# gps_and_sensor_board.net
KiCad netlist of a schematic drawn in EAGLE
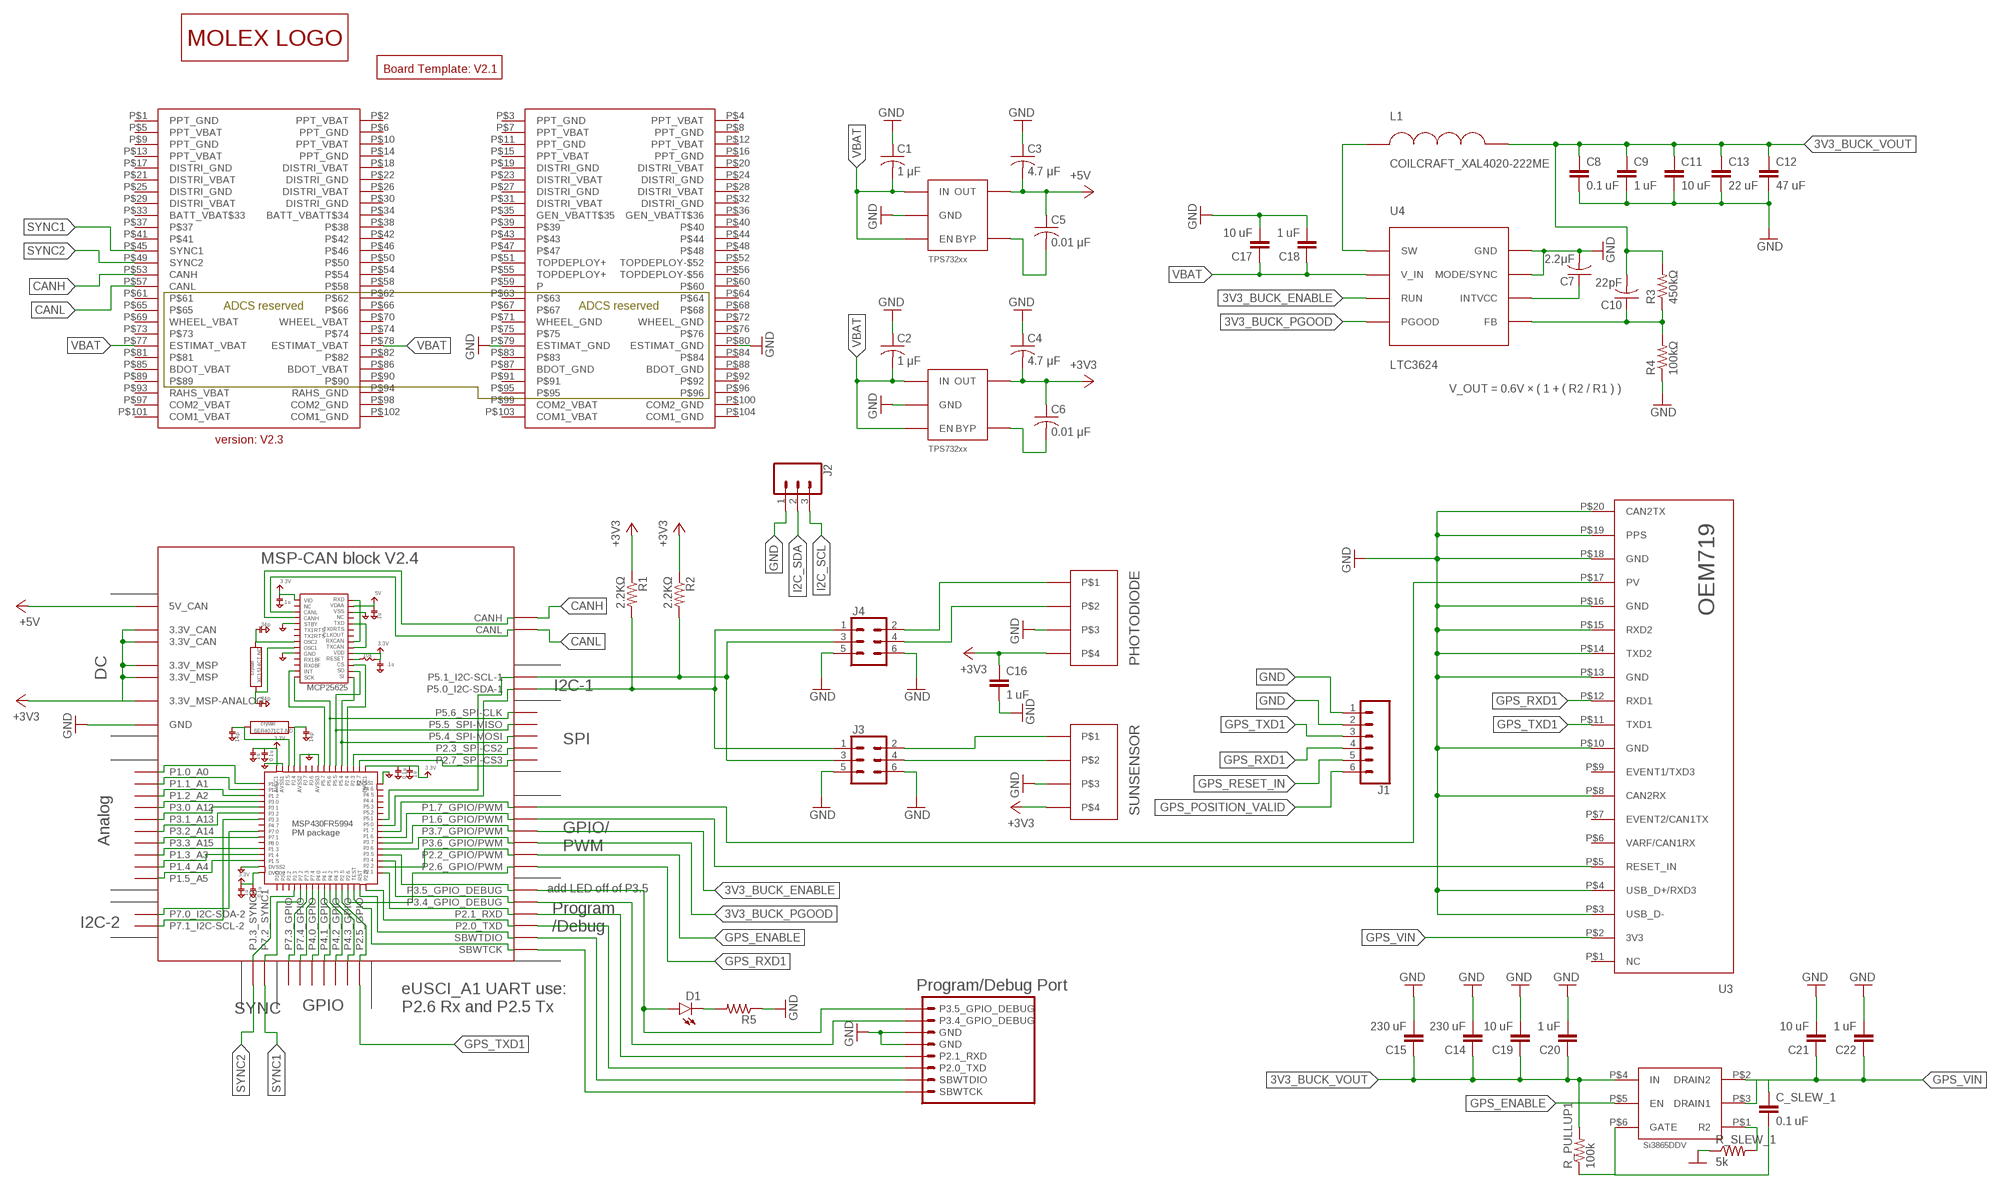
[diagram p0: schematic, sheet 1]

(export (version "E")
  (design (tool "Eeschema 10.0.6"))
  (components
    (comp (ref "B1")
      (value "BOARD_TEMPLATE1")
      (footprint "eagle-import:BOARD_TEMPLATE")
      (libsource (lib "eagle-import") (part "BOARD_TEMPLATE1"))
    )
    (comp (ref "BLK1")
      (value "MSP-CAN_BLOCK")
      (footprint "eagle-import:MSP-CAN_BLOCK")
      (libsource (lib "eagle-import") (part "MSP-CAN_BLOCK"))
    )
    (comp (ref "C1")
      (value "1 μF")
      (footprint "eagle-import:C0805")
      (libsource (lib "eagle-import") (part "C-USC0805"))
    )
    (comp (ref "C2")
      (value "1 μF")
      (footprint "eagle-import:C0805")
      (libsource (lib "eagle-import") (part "C-USC0805"))
    )
    (comp (ref "C3")
      (value "4.7 μF")
      (footprint "eagle-import:C0805")
      (libsource (lib "eagle-import") (part "C-USC0805"))
    )
    (comp (ref "C4")
      (value "4.7 μF")
      (footprint "eagle-import:C0805")
      (libsource (lib "eagle-import") (part "C-USC0805"))
    )
    (comp (ref "C5")
      (value "0.01 μF")
      (footprint "eagle-import:C0805")
      (libsource (lib "eagle-import") (part "C-USC0805"))
    )
    (comp (ref "C6")
      (value "0.01 μF")
      (footprint "eagle-import:C0805")
      (libsource (lib "eagle-import") (part "C-USC0805"))
    )
    (comp (ref "C7")
      (value "2.2μF")
      (footprint "eagle-import:C0805")
      (libsource (lib "eagle-import") (part "C-USC0805"))
    )
    (comp (ref "C8")
      (value "0.1 uF")
      (footprint "eagle-import:0805")
      (libsource (lib "eagle-import") (part "CAPACITOR0805"))
    )
    (comp (ref "C9")
      (value "1 uF")
      (footprint "eagle-import:0805")
      (libsource (lib "eagle-import") (part "CAPACITOR0805"))
    )
    (comp (ref "C10")
      (value "22pF")
      (footprint "eagle-import:C0805")
      (libsource (lib "eagle-import") (part "C-USC0805"))
    )
    (comp (ref "C11")
      (value "10 uF")
      (footprint "eagle-import:0805")
      (libsource (lib "eagle-import") (part "CAPACITOR0805"))
    )
    (comp (ref "C12")
      (value "47 uF")
      (footprint "eagle-import:1206")
      (libsource (lib "eagle-import") (part "CAPACITOR1206"))
    )
    (comp (ref "C13")
      (value "22 uF")
      (footprint "eagle-import:1206")
      (libsource (lib "eagle-import") (part "CAPACITOR1206"))
    )
    (comp (ref "C14")
      (value "230 uF")
      (footprint "eagle-import:PANASONIC_SVPG")
      (libsource (lib "eagle-import") (part "CAPACITORPANASONIC_16SVPG270M"))
    )
    (comp (ref "C15")
      (value "230 uF")
      (footprint "eagle-import:PANASONIC_SVPG")
      (libsource (lib "eagle-import") (part "CAPACITORPANASONIC_16SVPG270M"))
    )
    (comp (ref "C16")
      (value "1 uF")
      (footprint "eagle-import:0805")
      (libsource (lib "eagle-import") (part "CAPACITOR0805"))
    )
    (comp (ref "C17")
      (value "10 uF")
      (footprint "eagle-import:0805")
      (libsource (lib "eagle-import") (part "CAPACITOR0805"))
    )
    (comp (ref "C18")
      (value "1 uF")
      (footprint "eagle-import:0805")
      (libsource (lib "eagle-import") (part "CAPACITOR0805"))
    )
    (comp (ref "C19")
      (value "10 uF")
      (footprint "eagle-import:0805")
      (libsource (lib "eagle-import") (part "CAPACITOR0805"))
    )
    (comp (ref "C20")
      (value "1 uF")
      (footprint "eagle-import:0805")
      (libsource (lib "eagle-import") (part "CAPACITOR0805"))
    )
    (comp (ref "C21")
      (value "10 uF")
      (footprint "eagle-import:0805")
      (libsource (lib "eagle-import") (part "CAPACITOR0805"))
    )
    (comp (ref "C22")
      (value "1 uF")
      (footprint "eagle-import:0805")
      (libsource (lib "eagle-import") (part "CAPACITOR0805"))
    )
    (comp (ref "CONN1")
      (value "PC104_CONNECTOR")
      (footprint "eagle-import:PC104_CONNECTOR")
      (libsource (lib "eagle-import") (part "PC104_CONNECTOR"))
    )
    (comp (ref "C_SLEW_1")
      (value "0.1 uF")
      (footprint "eagle-import:0805")
      (libsource (lib "eagle-import") (part "CAPACITOR0805"))
    )
    (comp (ref "D1")
      (value "LED")
      (footprint "eagle-import:LED-1206")
      (libsource (lib "eagle-import") (part "LED"))
    )
    (comp (ref "J1")
      (value "CONN_06LOCK")
      (footprint "eagle-import:1X06_LOCK")
      (libsource (lib "eagle-import") (part "CONN_06LOCK"))
    )
    (comp (ref "J2")
      (value "CONN_03LOCK")
      (footprint "eagle-import:1X03_LOCK")
      (libsource (lib "eagle-import") (part "CONN_03LOCK"))
    )
    (comp (ref "J3")
      (value "CONN_03X22X3_SILK_MALE_PTH")
      (footprint "eagle-import:2X3")
      (libsource (lib "eagle-import") (part "CONN_03X22X3_SILK_MALE_PTH"))
    )
    (comp (ref "J4")
      (value "CONN_03X22X3_SILK_MALE_PTH")
      (footprint "eagle-import:2X3")
      (libsource (lib "eagle-import") (part "CONN_03X22X3_SILK_MALE_PTH"))
    )
    (comp (ref "L1")
      (value "COILCRAFT_XAL4020-222ME")
      (footprint "eagle-import:COILCRAFT_XAL4020")
      (libsource (lib "eagle-import") (part "COILCRAFT_XAL4020-222ME"))
    )
    (comp (ref "PHOTODIODE")
      (value "PICOLOCK_4")
      (footprint "eagle-import:PICOLOCK_4")
      (libsource (lib "eagle-import") (part "PICOLOCK_4"))
    )
    (comp (ref "R1")
      (value "2.2KΩ")
      (footprint "eagle-import:R0805")
      (libsource (lib "eagle-import") (part "R-US_R0805"))
    )
    (comp (ref "R2")
      (value "2.2KΩ")
      (footprint "eagle-import:R0805")
      (libsource (lib "eagle-import") (part "R-US_R0805"))
    )
    (comp (ref "R3")
      (value "450kΩ")
      (footprint "eagle-import:R0805")
      (libsource (lib "eagle-import") (part "R-US_R0805"))
    )
    (comp (ref "R4")
      (value "100kΩ")
      (footprint "eagle-import:R0805")
      (libsource (lib "eagle-import") (part "R-US_R0805"))
    )
    (comp (ref "R5")
      (value "RESISTOR0805")
      (footprint "eagle-import:0805")
      (libsource (lib "eagle-import") (part "RESISTOR0805"))
    )
    (comp (ref "R_PULLUP1")
      (value "100k")
      (footprint "eagle-import:0805")
      (libsource (lib "eagle-import") (part "RESISTOR0805"))
    )
    (comp (ref "R_SLEW_1")
      (value "5k")
      (footprint "eagle-import:0805")
      (libsource (lib "eagle-import") (part "RESISTOR0805"))
    )
    (comp (ref "SUNSENSOR")
      (value "PICOLOCK_4")
      (footprint "eagle-import:PICOLOCK_4")
      (libsource (lib "eagle-import") (part "PICOLOCK_4"))
    )
    (comp (ref "U$1")
      (value "LOGO_MOLEX")
      (footprint "eagle-import:LOGO_MOLEX")
      (libsource (lib "eagle-import") (part "LOGO_MOLEX"))
    )
    (comp (ref "U$2")
      (value "PROGRAM/DEBUG_PORT")
      (footprint "eagle-import:1X08_CONNECTOR")
      (libsource (lib "eagle-import") (part "PROGRAM/DEBUG_PORT"))
    )
    (comp (ref "U$3")
      (value "SI3865DDV")
      (footprint "eagle-import:TSOP-6")
      (libsource (lib "eagle-import") (part "SI3865DDV"))
    )
    (comp (ref "U1")
      (value "TPS732XX")
      (footprint "eagle-import:SOT-23-5")
      (libsource (lib "eagle-import") (part "TPS732XX"))
    )
    (comp (ref "U2")
      (value "TPS732XX")
      (footprint "eagle-import:SOT-23-5")
      (libsource (lib "eagle-import") (part "TPS732XX"))
    )
    (comp (ref "U3")
      (value "OEM719")
      (footprint "eagle-import:OEM719")
      (libsource (lib "eagle-import") (part "OEM719"))
    )
    (comp (ref "U4")
      (value "LTC3624")
      (footprint "eagle-import:LTC3624")
      (libsource (lib "eagle-import") (part "LTC3624"))
    )
  )
  (nets
    (net (code "1") (name "+3V3") (class "Default")
      (node (ref "BLK1") (pin "3.3V@CAN1") (pinfunction "3.3V_CAN_3.3V@CAN1") (pintype "bidirectional"))
      (node (ref "BLK1") (pin "3.3V@CAN2") (pinfunction "3.3V_CAN_3.3V@CAN2") (pintype "bidirectional"))
      (node (ref "BLK1") (pin "3.3V@MSP1") (pinfunction "3.3V_MSP_3.3V@MSP1") (pintype "bidirectional"))
      (node (ref "BLK1") (pin "3.3V@MSP2") (pinfunction "3.3V_MSP_3.3V@MSP2") (pintype "bidirectional"))
      (node (ref "BLK1") (pin "3.3V_ANALOG@MSP2") (pinfunction "3.3V_MSP-ANALOG_3.3V_ANALOG@MSP2") (pintype "bidirectional"))
      (node (ref "C16") (pin "1") (pinfunction "1_1") (pintype "passive"))
      (node (ref "C4") (pin "2") (pinfunction "2_2") (pintype "passive"))
      (node (ref "C6") (pin "1") (pinfunction "1_1") (pintype "passive"))
      (node (ref "PHOTODIODE") (pin "P$4") (pinfunction "P$4_P$4") (pintype "bidirectional"))
      (node (ref "R1") (pin "1") (pinfunction "1_1") (pintype "passive"))
      (node (ref "R2") (pin "1") (pinfunction "1_1") (pintype "passive"))
      (node (ref "SUNSENSOR") (pin "P$4") (pinfunction "P$4_P$4") (pintype "bidirectional"))
      (node (ref "U2") (pin "P$5") (pinfunction "OUT_P$5") (pintype "bidirectional"))
    )
    (net (code "2") (name "+5V") (class "Default")
      (node (ref "BLK1") (pin "5V") (pinfunction "5V_CAN_5V") (pintype "bidirectional"))
      (node (ref "C3") (pin "2") (pinfunction "2_2") (pintype "passive"))
      (node (ref "C5") (pin "1") (pinfunction "1_1") (pintype "passive"))
      (node (ref "U1") (pin "P$5") (pinfunction "OUT_P$5") (pintype "bidirectional"))
    )
    (net (code "3") (name "3V3_BUCK_ENABLE") (class "Default")
      (node (ref "BLK1") (pin "P3.7_GPIO/PWM") (pinfunction "P3.7_GPIO/PWM_P3.7_GPIO/PWM") (pintype "bidirectional"))
      (node (ref "U4") (pin "RUN") (pinfunction "RUN_RUN") (pintype "bidirectional"))
    )
    (net (code "4") (name "3V3_BUCK_PGOOD") (class "Default")
      (node (ref "BLK1") (pin "P3.6_GPIO/PWM") (pinfunction "P3.6_GPIO/PWM_P3.6_GPIO/PWM") (pintype "bidirectional"))
      (node (ref "U4") (pin "PGOOD") (pinfunction "PGOOD_PGOOD") (pintype "bidirectional"))
    )
    (net (code "5") (name "3V3_BUCK_VOUT") (class "Default")
      (node (ref "C10") (pin "2") (pinfunction "2_2") (pintype "passive"))
      (node (ref "C11") (pin "1") (pinfunction "1_1") (pintype "passive"))
      (node (ref "C12") (pin "1") (pinfunction "1_1") (pintype "passive"))
      (node (ref "C13") (pin "1") (pinfunction "1_1") (pintype "passive"))
      (node (ref "C14") (pin "POS") (pinfunction "1_POS") (pintype "passive"))
      (node (ref "C15") (pin "POS") (pinfunction "1_POS") (pintype "passive"))
      (node (ref "C19") (pin "1") (pinfunction "1_1") (pintype "passive"))
      (node (ref "C20") (pin "1") (pinfunction "1_1") (pintype "passive"))
      (node (ref "C8") (pin "1") (pinfunction "1_1") (pintype "passive"))
      (node (ref "C9") (pin "1") (pinfunction "1_1") (pintype "passive"))
      (node (ref "L1") (pin "P$2") (pinfunction "P$2_P$2") (pintype "bidirectional"))
      (node (ref "R3") (pin "2") (pinfunction "2_2") (pintype "passive"))
      (node (ref "R_PULLUP1") (pin "2") (pinfunction "2_2") (pintype "passive"))
      (node (ref "U$3") (pin "P$4") (pinfunction "IN_P$4") (pintype "bidirectional"))
    )
    (net (code "6") (name "CANH") (class "Default")
      (node (ref "BLK1") (pin "CANH") (pinfunction "CANH_CANH") (pintype "bidirectional"))
      (node (ref "CONN1") (pin "P$53") (pinfunction "CANH_P$53") (pintype "bidirectional"))
    )
    (net (code "7") (name "CANL") (class "Default")
      (node (ref "BLK1") (pin "CANL") (pinfunction "CANL_CANL") (pintype "bidirectional"))
      (node (ref "CONN1") (pin "P$57") (pinfunction "CANL_P$57") (pintype "bidirectional"))
    )
    (net (code "8") (name "GND") (class "Default")
      (node (ref "BLK1") (pin "GND@1") (pinfunction "GND_GND@1") (pintype "bidirectional"))
      (node (ref "BLK1") (pin "GND@10") (pinfunction "GND_GND@10") (pintype "bidirectional"))
      (node (ref "BLK1") (pin "GND@11") (pinfunction "GND_GND@11") (pintype "bidirectional"))
      (node (ref "BLK1") (pin "GND@12") (pinfunction "GND_GND@12") (pintype "bidirectional"))
      (node (ref "BLK1") (pin "GND@13") (pinfunction "GND_GND@13") (pintype "bidirectional"))
      (node (ref "BLK1") (pin "GND@14") (pinfunction "GND_GND@14") (pintype "bidirectional"))
      (node (ref "BLK1") (pin "GND@15") (pinfunction "GND_GND@15") (pintype "bidirectional"))
      (node (ref "BLK1") (pin "GND@16") (pinfunction "GND_GND@16") (pintype "bidirectional"))
      (node (ref "BLK1") (pin "GND@17") (pinfunction "GND_GND@17") (pintype "bidirectional"))
      (node (ref "BLK1") (pin "GND@2") (pinfunction "GND_GND@2") (pintype "bidirectional"))
      (node (ref "BLK1") (pin "GND@26") (pinfunction "GND_GND@26") (pintype "bidirectional"))
      (node (ref "BLK1") (pin "GND@3") (pinfunction "GND_GND@3") (pintype "bidirectional"))
      (node (ref "BLK1") (pin "GND@4") (pinfunction "GND_GND@4") (pintype "bidirectional"))
      (node (ref "BLK1") (pin "GND@5") (pinfunction "GND_GND@5") (pintype "bidirectional"))
      (node (ref "BLK1") (pin "GND@7") (pinfunction "GND_GND@7") (pintype "bidirectional"))
      (node (ref "BLK1") (pin "GND@8") (pinfunction "GND_GND@8") (pintype "bidirectional"))
      (node (ref "BLK1") (pin "GND@9") (pinfunction "GND_GND@9") (pintype "bidirectional"))
      (node (ref "C1") (pin "1") (pinfunction "1_1") (pintype "passive"))
      (node (ref "C11") (pin "2") (pinfunction "2_2") (pintype "passive"))
      (node (ref "C12") (pin "2") (pinfunction "2_2") (pintype "passive"))
      (node (ref "C13") (pin "2") (pinfunction "2_2") (pintype "passive"))
      (node (ref "C14") (pin "NEG") (pinfunction "2_NEG") (pintype "passive"))
      (node (ref "C15") (pin "NEG") (pinfunction "2_NEG") (pintype "passive"))
      (node (ref "C16") (pin "2") (pinfunction "2_2") (pintype "passive"))
      (node (ref "C17") (pin "2") (pinfunction "2_2") (pintype "passive"))
      (node (ref "C18") (pin "2") (pinfunction "2_2") (pintype "passive"))
      (node (ref "C19") (pin "2") (pinfunction "2_2") (pintype "passive"))
      (node (ref "C2") (pin "1") (pinfunction "1_1") (pintype "passive"))
      (node (ref "C20") (pin "2") (pinfunction "2_2") (pintype "passive"))
      (node (ref "C21") (pin "2") (pinfunction "2_2") (pintype "passive"))
      (node (ref "C22") (pin "2") (pinfunction "2_2") (pintype "passive"))
      (node (ref "C3") (pin "1") (pinfunction "1_1") (pintype "passive"))
      (node (ref "C4") (pin "1") (pinfunction "1_1") (pintype "passive"))
      (node (ref "C7") (pin "2") (pinfunction "2_2") (pintype "passive"))
      (node (ref "C8") (pin "2") (pinfunction "2_2") (pintype "passive"))
      (node (ref "C9") (pin "2") (pinfunction "2_2") (pintype "passive"))
      (node (ref "CONN1") (pin "P$79") (pinfunction "ESTIMAT_GND_P$79") (pintype "bidirectional"))
      (node (ref "CONN1") (pin "P$80") (pinfunction "ESTIMAT_GND_P$80") (pintype "bidirectional"))
      (node (ref "J1") (pin "1") (pinfunction "1_1") (pintype "passive"))
      (node (ref "J1") (pin "2") (pinfunction "2_2") (pintype "passive"))
      (node (ref "J2") (pin "1") (pinfunction "1_1") (pintype "passive"))
      (node (ref "J3") (pin "5") (pinfunction "5_5") (pintype "bidirectional"))
      (node (ref "J3") (pin "6") (pinfunction "6_6") (pintype "bidirectional"))
      (node (ref "J4") (pin "5") (pinfunction "5_5") (pintype "bidirectional"))
      (node (ref "J4") (pin "6") (pinfunction "6_6") (pintype "bidirectional"))
      (node (ref "PHOTODIODE") (pin "P$3") (pinfunction "P$3_P$3") (pintype "bidirectional"))
      (node (ref "R4") (pin "1") (pinfunction "1_1") (pintype "passive"))
      (node (ref "R5") (pin "1") (pinfunction "1_1") (pintype "passive"))
      (node (ref "R_SLEW_1") (pin "1") (pinfunction "1_1") (pintype "passive"))
      (node (ref "SUNSENSOR") (pin "P$3") (pinfunction "P$3_P$3") (pintype "bidirectional"))
      (node (ref "U$2") (pin "5") (pinfunction "GND_5") (pintype "bidirectional"))
      (node (ref "U$2") (pin "6") (pinfunction "GND_6") (pintype "bidirectional"))
      (node (ref "U1") (pin "P$2") (pinfunction "GND_P$2") (pintype "bidirectional"))
      (node (ref "U2") (pin "P$2") (pinfunction "GND_P$2") (pintype "bidirectional"))
      (node (ref "U3") (pin "P$10") (pinfunction "GND_P$10") (pintype "bidirectional"))
      (node (ref "U3") (pin "P$13") (pinfunction "GND_P$13") (pintype "bidirectional"))
      (node (ref "U3") (pin "P$14") (pinfunction "TXD2_P$14") (pintype "bidirectional"))
      (node (ref "U3") (pin "P$15") (pinfunction "RXD2_P$15") (pintype "bidirectional"))
      (node (ref "U3") (pin "P$16") (pinfunction "GND_P$16") (pintype "bidirectional"))
      (node (ref "U3") (pin "P$18") (pinfunction "GND_P$18") (pintype "bidirectional"))
      (node (ref "U3") (pin "P$19") (pinfunction "PPS_P$19") (pintype "bidirectional"))
      (node (ref "U3") (pin "P$20") (pinfunction "CAN2TX_P$20") (pintype "bidirectional"))
      (node (ref "U3") (pin "P$3") (pinfunction "USB_D-_P$3") (pintype "bidirectional"))
      (node (ref "U3") (pin "P$4") (pinfunction "USB_D+/RXD3_P$4") (pintype "bidirectional"))
      (node (ref "U3") (pin "P$8") (pinfunction "CAN2RX_P$8") (pintype "bidirectional"))
      (node (ref "U4") (pin "GND@1") (pinfunction "GND_GND@1") (pintype "bidirectional"))
      (node (ref "U4") (pin "GND@PAD") (pinfunction "GND_GND@PAD") (pintype "bidirectional"))
      (node (ref "U4") (pin "MODE/SYNC") (pinfunction "MODE/SYNC_MODE/SYNC") (pintype "bidirectional"))
    )
    (net (code "9") (name "GPS_ENABLE") (class "Default")
      (node (ref "BLK1") (pin "P2.2_GPIO/PWM") (pinfunction "P2.2_GPIO/PWM_P2.2_GPIO/PWM") (pintype "bidirectional"))
      (node (ref "U$3") (pin "P$5") (pinfunction "EN_P$5") (pintype "bidirectional"))
    )
    (net (code "10") (name "GPS_POSITION_VALID") (class "Default")
      (node (ref "BLK1") (pin "P1.7_GPIO/PWM") (pinfunction "P1.7_GPIO/PWM_P1.7_GPIO/PWM") (pintype "bidirectional"))
      (node (ref "J1") (pin "6") (pinfunction "6_6") (pintype "passive"))
      (node (ref "U3") (pin "P$17") (pinfunction "PV_P$17") (pintype "bidirectional"))
    )
    (net (code "11") (name "GPS_RESET_IN") (class "Default")
      (node (ref "BLK1") (pin "P1.6_GPIO/PWM") (pinfunction "P1.6_GPIO/PWM_P1.6_GPIO/PWM") (pintype "bidirectional"))
      (node (ref "J1") (pin "5") (pinfunction "5_5") (pintype "passive"))
      (node (ref "U3") (pin "P$5") (pinfunction "RESET_IN_P$5") (pintype "bidirectional"))
    )
    (net (code "12") (name "GPS_RXD1") (class "Default")
      (node (ref "BLK1") (pin "P2.6_GPIO/PWM") (pinfunction "P2.6_GPIO/PWM_P2.6_GPIO/PWM") (pintype "bidirectional"))
      (node (ref "J1") (pin "4") (pinfunction "4_4") (pintype "passive"))
      (node (ref "U3") (pin "P$12") (pinfunction "RXD1_P$12") (pintype "bidirectional"))
    )
    (net (code "13") (name "GPS_TXD1") (class "Default")
      (node (ref "BLK1") (pin "P2.5_GPIO") (pinfunction "P2.5_GPIO_P2.5_GPIO") (pintype "bidirectional"))
      (node (ref "J1") (pin "3") (pinfunction "3_3") (pintype "passive"))
      (node (ref "U3") (pin "P$11") (pinfunction "TXD1_P$11") (pintype "bidirectional"))
    )
    (net (code "14") (name "GPS_VIN") (class "Default")
      (node (ref "C21") (pin "1") (pinfunction "1_1") (pintype "passive"))
      (node (ref "C22") (pin "1") (pinfunction "1_1") (pintype "passive"))
      (node (ref "C_SLEW_1") (pin "1") (pinfunction "1_1") (pintype "passive"))
      (node (ref "U$3") (pin "P$2") (pinfunction "DRAIN2_P$2") (pintype "bidirectional"))
      (node (ref "U$3") (pin "P$3") (pinfunction "DRAIN1_P$3") (pintype "bidirectional"))
      (node (ref "U3") (pin "P$2") (pinfunction "3V3_P$2") (pintype "bidirectional"))
    )
    (net (code "15") (name "I2C_SCL") (class "Default")
      (node (ref "BLK1") (pin "P5.1_I2C-SCL-1") (pinfunction "P5.1_I2C-SCL-1_P5.1_I2C-SCL-1") (pintype "bidirectional"))
      (node (ref "J2") (pin "3") (pinfunction "3_3") (pintype "passive"))
      (node (ref "J3") (pin "3") (pinfunction "3_3") (pintype "bidirectional"))
      (node (ref "J4") (pin "3") (pinfunction "3_3") (pintype "bidirectional"))
      (node (ref "R2") (pin "2") (pinfunction "2_2") (pintype "passive"))
    )
    (net (code "16") (name "I2C_SDA") (class "Default")
      (node (ref "BLK1") (pin "P5.0_I2C-SDA-1") (pinfunction "P5.0_I2C-SDA-1_P5.0_I2C-SDA-1") (pintype "bidirectional"))
      (node (ref "J2") (pin "2") (pinfunction "2_2") (pintype "passive"))
      (node (ref "J3") (pin "1") (pinfunction "1_1") (pintype "bidirectional"))
      (node (ref "J4") (pin "1") (pinfunction "1_1") (pintype "bidirectional"))
      (node (ref "R1") (pin "2") (pinfunction "2_2") (pintype "passive"))
    )
    (net (code "17") (name "Net-(BLK1-PadSBWTCK)") (class "Default")
      (node (ref "BLK1") (pin "SBWTCK") (pinfunction "SBWTCK_SBWTCK") (pintype "bidirectional"))
      (node (ref "U$2") (pin "SBWTCK") (pinfunction "SBWTCK_SBWTCK") (pintype "bidirectional"))
    )
    (net (code "18") (name "Net-(C7-Pad1)") (class "Default")
      (node (ref "C7") (pin "1") (pinfunction "1_1") (pintype "passive"))
      (node (ref "U4") (pin "INTVCC") (pinfunction "INTVCC_INTVCC") (pintype "bidirectional"))
    )
    (net (code "19") (name "Net-(C10-Pad1)") (class "Default")
      (node (ref "C10") (pin "1") (pinfunction "1_1") (pintype "passive"))
      (node (ref "R3") (pin "1") (pinfunction "1_1") (pintype "passive"))
      (node (ref "R4") (pin "2") (pinfunction "2_2") (pintype "passive"))
      (node (ref "U4") (pin "FB") (pinfunction "FB_FB") (pintype "bidirectional"))
    )
    (net (code "20") (name "Net-(D1-PadC)") (class "Default")
      (node (ref "D1") (pin "C") (pinfunction "C_C") (pintype "passive"))
      (node (ref "R5") (pin "2") (pinfunction "2_2") (pintype "passive"))
    )
    (net (code "21") (name "Net-(J3-Pad2)") (class "Default")
      (node (ref "J3") (pin "2") (pinfunction "2_2") (pintype "bidirectional"))
      (node (ref "SUNSENSOR") (pin "P$1") (pinfunction "P$1_P$1") (pintype "bidirectional"))
    )
    (net (code "22") (name "Net-(J3-Pad4)") (class "Default")
      (node (ref "J3") (pin "4") (pinfunction "4_4") (pintype "bidirectional"))
      (node (ref "SUNSENSOR") (pin "P$2") (pinfunction "P$2_P$2") (pintype "bidirectional"))
    )
    (net (code "23") (name "Net-(J4-Pad2)") (class "Default")
      (node (ref "J4") (pin "2") (pinfunction "2_2") (pintype "bidirectional"))
      (node (ref "PHOTODIODE") (pin "P$1") (pinfunction "P$1_P$1") (pintype "bidirectional"))
    )
    (net (code "24") (name "Net-(J4-Pad4)") (class "Default")
      (node (ref "J4") (pin "4") (pinfunction "4_4") (pintype "bidirectional"))
      (node (ref "PHOTODIODE") (pin "P$2") (pinfunction "P$2_P$2") (pintype "bidirectional"))
    )
    (net (code "25") (name "Net-(L1-PadP$1)") (class "Default")
      (node (ref "L1") (pin "P$1") (pinfunction "P$1_P$1") (pintype "bidirectional"))
      (node (ref "U4") (pin "SW") (pinfunction "SW_SW") (pintype "bidirectional"))
    )
    (net (code "26") (name "Net-(U$2-P2.0_TXD)") (class "Default")
      (node (ref "BLK1") (pin "P2.0_TXD") (pinfunction "P2.0_TXD_P2.0_TXD") (pintype "bidirectional"))
      (node (ref "U$2") (pin "3") (pinfunction "P2.0_TXD_3") (pintype "bidirectional"))
    )
    (net (code "27") (name "Net-(U$2-P2.1_RXD)") (class "Default")
      (node (ref "BLK1") (pin "P2.1_RXD") (pinfunction "P2.1_RXD_P2.1_RXD") (pintype "bidirectional"))
      (node (ref "U$2") (pin "4") (pinfunction "P2.1_RXD_4") (pintype "bidirectional"))
    )
    (net (code "28") (name "Net-(U$2-P3.4_GPIO_DEBUG)") (class "Default")
      (node (ref "BLK1") (pin "P3.4_GPIO_DEBUG") (pinfunction "P3.4_GPIO_DEBUG_P3.4_GPIO_DEBUG") (pintype "bidirectional"))
      (node (ref "U$2") (pin "7") (pinfunction "P3.4_GPIO_DEBUG_7") (pintype "bidirectional"))
    )
    (net (code "29") (name "Net-(U$2-P3.5_GPIO_DEBUG)") (class "Default")
      (node (ref "BLK1") (pin "P3.5_GPIO_DEBUG") (pinfunction "P3.5_GPIO_DEBUG_P3.5_GPIO_DEBUG") (pintype "bidirectional"))
      (node (ref "D1") (pin "A") (pinfunction "A_A") (pintype "passive"))
      (node (ref "U$2") (pin "8") (pinfunction "P3.5_GPIO_DEBUG_8") (pintype "bidirectional"))
    )
    (net (code "30") (name "Net-(U$2-SBWTDIO)") (class "Default")
      (node (ref "BLK1") (pin "SBWTDIO") (pinfunction "SBWTDIO_SBWTDIO") (pintype "bidirectional"))
      (node (ref "U$2") (pin "2") (pinfunction "SBWTDIO_2") (pintype "bidirectional"))
    )
    (net (code "31") (name "Net-(U$3-GATE)") (class "Default")
      (node (ref "C_SLEW_1") (pin "2") (pinfunction "2_2") (pintype "passive"))
      (node (ref "R_PULLUP1") (pin "1") (pinfunction "1_1") (pintype "passive"))
      (node (ref "U$3") (pin "P$6") (pinfunction "GATE_P$6") (pintype "bidirectional"))
    )
    (net (code "32") (name "Net-(U$3-R2)") (class "Default")
      (node (ref "R_SLEW_1") (pin "2") (pinfunction "2_2") (pintype "passive"))
      (node (ref "U$3") (pin "P$1") (pinfunction "R2_P$1") (pintype "bidirectional"))
    )
    (net (code "33") (name "Net-(U1-BYP)") (class "Default")
      (node (ref "C5") (pin "2") (pinfunction "2_2") (pintype "passive"))
      (node (ref "U1") (pin "P$4") (pinfunction "BYP_P$4") (pintype "bidirectional"))
    )
    (net (code "34") (name "Net-(U2-BYP)") (class "Default")
      (node (ref "C6") (pin "2") (pinfunction "2_2") (pintype "passive"))
      (node (ref "U2") (pin "P$4") (pinfunction "BYP_P$4") (pintype "bidirectional"))
    )
    (net (code "35") (name "SYNC1") (class "Default")
      (node (ref "BLK1") (pin "P7.2_SYNC1") (pinfunction "P7.2_SYNC1_P7.2_SYNC1") (pintype "bidirectional"))
      (node (ref "CONN1") (pin "P$45") (pinfunction "SYNC1_P$45") (pintype "bidirectional"))
    )
    (net (code "36") (name "SYNC2") (class "Default")
      (node (ref "BLK1") (pin "PJ.3_SYNC2") (pinfunction "PJ.3_SYNC2_PJ.3_SYNC2") (pintype "bidirectional"))
      (node (ref "CONN1") (pin "P$49") (pinfunction "SYNC2_P$49") (pintype "bidirectional"))
    )
    (net (code "37") (name "VBAT") (class "Default")
      (node (ref "C1") (pin "2") (pinfunction "2_2") (pintype "passive"))
      (node (ref "C17") (pin "1") (pinfunction "1_1") (pintype "passive"))
      (node (ref "C18") (pin "1") (pinfunction "1_1") (pintype "passive"))
      (node (ref "C2") (pin "2") (pinfunction "2_2") (pintype "passive"))
      (node (ref "CONN1") (pin "P$77") (pinfunction "ESTIMAT_VBAT_P$77") (pintype "bidirectional"))
      (node (ref "CONN1") (pin "P$78") (pinfunction "ESTIMAT_VBAT_P$78") (pintype "bidirectional"))
      (node (ref "U1") (pin "P$1") (pinfunction "IN_P$1") (pintype "bidirectional"))
      (node (ref "U1") (pin "P$3") (pinfunction "EN_P$3") (pintype "bidirectional"))
      (node (ref "U2") (pin "P$1") (pinfunction "IN_P$1") (pintype "bidirectional"))
      (node (ref "U2") (pin "P$3") (pinfunction "EN_P$3") (pintype "bidirectional"))
      (node (ref "U4") (pin "V_IN") (pinfunction "V_IN_V_IN") (pintype "bidirectional"))
    )
    (net (code "38") (name "unconnected-(BLK1-P2.3_SPI-CS2-PadP2.4_SPI-CS2)") (class "Default")
      (node (ref "BLK1") (pin "P2.4_SPI-CS2") (pinfunction "P2.3_SPI-CS2_P2.4_SPI-CS2") (pintype "bidirectional"))
    )
    (net (code "39") (name "unconnected-(BLK1-PadP1.0_A0)") (class "Default")
      (node (ref "BLK1") (pin "P1.0_A0") (pinfunction "P1.0_A0_P1.0_A0") (pintype "bidirectional"))
    )
    (net (code "40") (name "unconnected-(BLK1-PadP1.1_A1)") (class "Default")
      (node (ref "BLK1") (pin "P1.1_A1") (pinfunction "P1.1_A1_P1.1_A1") (pintype "bidirectional"))
    )
    (net (code "41") (name "unconnected-(BLK1-PadP1.2_A2)") (class "Default")
      (node (ref "BLK1") (pin "P1.2_A2") (pinfunction "P1.2_A2_P1.2_A2") (pintype "bidirectional"))
    )
    (net (code "42") (name "unconnected-(BLK1-PadP1.3_A3)") (class "Default")
      (node (ref "BLK1") (pin "P1.3_A3") (pinfunction "P1.3_A3_P1.3_A3") (pintype "bidirectional"))
    )
    (net (code "43") (name "unconnected-(BLK1-PadP1.4_A4)") (class "Default")
      (node (ref "BLK1") (pin "P1.4_A4") (pinfunction "P1.4_A4_P1.4_A4") (pintype "bidirectional"))
    )
    (net (code "44") (name "unconnected-(BLK1-PadP1.5_A5)") (class "Default")
      (node (ref "BLK1") (pin "P1.5_A5") (pinfunction "P1.5_A5_P1.5_A5") (pintype "bidirectional"))
    )
    (net (code "45") (name "unconnected-(BLK1-PadP2.7_SPI-CS3)") (class "Default")
      (node (ref "BLK1") (pin "P2.7_SPI-CS3") (pinfunction "P2.7_SPI-CS3_P2.7_SPI-CS3") (pintype "bidirectional"))
    )
    (net (code "46") (name "unconnected-(BLK1-PadP3.0_A12)") (class "Default")
      (node (ref "BLK1") (pin "P3.0_A12") (pinfunction "P3.0_A12_P3.0_A12") (pintype "bidirectional"))
    )
    (net (code "47") (name "unconnected-(BLK1-PadP3.1_A13)") (class "Default")
      (node (ref "BLK1") (pin "P3.1_A13") (pinfunction "P3.1_A13_P3.1_A13") (pintype "bidirectional"))
    )
    (net (code "48") (name "unconnected-(BLK1-PadP3.2_A14)") (class "Default")
      (node (ref "BLK1") (pin "P3.2_A14") (pinfunction "P3.2_A14_P3.2_A14") (pintype "bidirectional"))
    )
    (net (code "49") (name "unconnected-(BLK1-PadP3.3_A15)") (class "Default")
      (node (ref "BLK1") (pin "P3.3_A15") (pinfunction "P3.3_A15_P3.3_A15") (pintype "bidirectional"))
    )
    (net (code "50") (name "unconnected-(BLK1-PadP4.0_GPIO)") (class "Default")
      (node (ref "BLK1") (pin "P4.0_GPIO") (pinfunction "P4.0_GPIO_P4.0_GPIO") (pintype "bidirectional"))
    )
    (net (code "51") (name "unconnected-(BLK1-PadP4.1_GPIO)") (class "Default")
      (node (ref "BLK1") (pin "P4.1_GPIO") (pinfunction "P4.1_GPIO_P4.1_GPIO") (pintype "bidirectional"))
    )
    (net (code "52") (name "unconnected-(BLK1-PadP4.2_GPIO)") (class "Default")
      (node (ref "BLK1") (pin "P4.2_GPIO") (pinfunction "P4.2_GPIO_P4.2_GPIO") (pintype "bidirectional"))
    )
    (net (code "53") (name "unconnected-(BLK1-PadP4.3_GPIO)") (class "Default")
      (node (ref "BLK1") (pin "P4.3_GPIO") (pinfunction "P4.3_GPIO_P4.3_GPIO") (pintype "bidirectional"))
    )
    (net (code "54") (name "unconnected-(BLK1-PadP5.4_SPI-MOSI)") (class "Default")
      (node (ref "BLK1") (pin "P5.4_SPI-MOSI") (pinfunction "P5.4_SPI-MOSI_P5.4_SPI-MOSI") (pintype "bidirectional"))
    )
    (net (code "55") (name "unconnected-(BLK1-PadP5.5_SPI-MISO)") (class "Default")
      (node (ref "BLK1") (pin "P5.5_SPI-MISO") (pinfunction "P5.5_SPI-MISO_P5.5_SPI-MISO") (pintype "bidirectional"))
    )
    (net (code "56") (name "unconnected-(BLK1-PadP5.6_SPI-CLK)") (class "Default")
      (node (ref "BLK1") (pin "P5.6_SPI-CLK") (pinfunction "P5.6_SPI-CLK_P5.6_SPI-CLK") (pintype "bidirectional"))
    )
    (net (code "57") (name "unconnected-(BLK1-PadP7.0_I2C-SDA-2)") (class "Default")
      (node (ref "BLK1") (pin "P7.0_I2C-SDA-2") (pinfunction "P7.0_I2C-SDA-2_P7.0_I2C-SDA-2") (pintype "bidirectional"))
    )
    (net (code "58") (name "unconnected-(BLK1-PadP7.1_I2C-SCL-2)") (class "Default")
      (node (ref "BLK1") (pin "P7.1_I2C-SCL-2") (pinfunction "P7.1_I2C-SCL-2_P7.1_I2C-SCL-2") (pintype "bidirectional"))
    )
    (net (code "59") (name "unconnected-(BLK1-PadP7.3_GPIO)") (class "Default")
      (node (ref "BLK1") (pin "P7.3_GPIO") (pinfunction "P7.3_GPIO_P7.3_GPIO") (pintype "bidirectional"))
    )
    (net (code "60") (name "unconnected-(BLK1-PadP7.4_GPIO)") (class "Default")
      (node (ref "BLK1") (pin "P7.4_GPIO") (pinfunction "P7.4_GPIO_P7.4_GPIO") (pintype "bidirectional"))
    )
    (net (code "61") (name "unconnected-(CONN1-BATT_VBAT$33-PadP$33)") (class "Default")
      (node (ref "CONN1") (pin "P$33") (pinfunction "BATT_VBAT$33_P$33") (pintype "bidirectional"))
    )
    (net (code "62") (name "unconnected-(CONN1-BATT_VBATT$34-PadP$34)") (class "Default")
      (node (ref "CONN1") (pin "P$34") (pinfunction "BATT_VBATT$34_P$34") (pintype "bidirectional"))
    )
    (net (code "63") (name "unconnected-(CONN1-BDOT_GND-PadP$87)") (class "Default")
      (node (ref "CONN1") (pin "P$87") (pinfunction "BDOT_GND_P$87") (pintype "bidirectional"))
    )
    (net (code "64") (name "unconnected-(CONN1-BDOT_GND-PadP$88)") (class "Default")
      (node (ref "CONN1") (pin "P$88") (pinfunction "BDOT_GND_P$88") (pintype "bidirectional"))
    )
    (net (code "65") (name "unconnected-(CONN1-BDOT_VBAT-PadP$85)") (class "Default")
      (node (ref "CONN1") (pin "P$85") (pinfunction "BDOT_VBAT_P$85") (pintype "bidirectional"))
    )
    (net (code "66") (name "unconnected-(CONN1-BDOT_VBAT-PadP$86)") (class "Default")
      (node (ref "CONN1") (pin "P$86") (pinfunction "BDOT_VBAT_P$86") (pintype "bidirectional"))
    )
    (net (code "67") (name "unconnected-(CONN1-COM1_GND-PadP$102)") (class "Default")
      (node (ref "CONN1") (pin "P$102") (pinfunction "COM1_GND_P$102") (pintype "bidirectional"))
    )
    (net (code "68") (name "unconnected-(CONN1-COM1_GND-PadP$104)") (class "Default")
      (node (ref "CONN1") (pin "P$104") (pinfunction "COM1_GND_P$104") (pintype "bidirectional"))
    )
    (net (code "69") (name "unconnected-(CONN1-COM1_VBAT-PadP$101)") (class "Default")
      (node (ref "CONN1") (pin "P$101") (pinfunction "COM1_VBAT_P$101") (pintype "bidirectional"))
    )
    (net (code "70") (name "unconnected-(CONN1-COM1_VBAT-PadP$103)") (class "Default")
      (node (ref "CONN1") (pin "P$103") (pinfunction "COM1_VBAT_P$103") (pintype "bidirectional"))
    )
    (net (code "71") (name "unconnected-(CONN1-COM2_GND-PadP$98)") (class "Default")
      (node (ref "CONN1") (pin "P$98") (pinfunction "COM2_GND_P$98") (pintype "bidirectional"))
    )
    (net (code "72") (name "unconnected-(CONN1-COM2_GND-PadP$100)") (class "Default")
      (node (ref "CONN1") (pin "P$100") (pinfunction "COM2_GND_P$100") (pintype "bidirectional"))
    )
    (net (code "73") (name "unconnected-(CONN1-COM2_VBAT-PadP$97)") (class "Default")
      (node (ref "CONN1") (pin "P$97") (pinfunction "COM2_VBAT_P$97") (pintype "bidirectional"))
    )
    (net (code "74") (name "unconnected-(CONN1-COM2_VBAT-PadP$99)") (class "Default")
      (node (ref "CONN1") (pin "P$99") (pinfunction "COM2_VBAT_P$99") (pintype "bidirectional"))
    )
    (net (code "75") (name "unconnected-(CONN1-DISTRI_GND-PadP$17)") (class "Default")
      (node (ref "CONN1") (pin "P$17") (pinfunction "DISTRI_GND_P$17") (pintype "bidirectional"))
    )
    (net (code "76") (name "unconnected-(CONN1-DISTRI_GND-PadP$19)") (class "Default")
      (node (ref "CONN1") (pin "P$19") (pinfunction "DISTRI_GND_P$19") (pintype "bidirectional"))
    )
    (net (code "77") (name "unconnected-(CONN1-DISTRI_GND-PadP$22)") (class "Default")
      (node (ref "CONN1") (pin "P$22") (pinfunction "DISTRI_GND_P$22") (pintype "bidirectional"))
    )
    (net (code "78") (name "unconnected-(CONN1-DISTRI_GND-PadP$24)") (class "Default")
      (node (ref "CONN1") (pin "P$24") (pinfunction "DISTRI_GND_P$24") (pintype "bidirectional"))
    )
    (net (code "79") (name "unconnected-(CONN1-DISTRI_GND-PadP$25)") (class "Default")
      (node (ref "CONN1") (pin "P$25") (pinfunction "DISTRI_GND_P$25") (pintype "bidirectional"))
    )
    (net (code "80") (name "unconnected-(CONN1-DISTRI_GND-PadP$27)") (class "Default")
      (node (ref "CONN1") (pin "P$27") (pinfunction "DISTRI_GND_P$27") (pintype "bidirectional"))
    )
    (net (code "81") (name "unconnected-(CONN1-DISTRI_GND-PadP$30)") (class "Default")
      (node (ref "CONN1") (pin "P$30") (pinfunction "DISTRI_GND_P$30") (pintype "bidirectional"))
    )
    (net (code "82") (name "unconnected-(CONN1-DISTRI_GND-PadP$32)") (class "Default")
      (node (ref "CONN1") (pin "P$32") (pinfunction "DISTRI_GND_P$32") (pintype "bidirectional"))
    )
    (net (code "83") (name "unconnected-(CONN1-DISTRI_VBAT-PadP$18)") (class "Default")
      (node (ref "CONN1") (pin "P$18") (pinfunction "DISTRI_VBAT_P$18") (pintype "bidirectional"))
    )
    (net (code "84") (name "unconnected-(CONN1-DISTRI_VBAT-PadP$20)") (class "Default")
      (node (ref "CONN1") (pin "P$20") (pinfunction "DISTRI_VBAT_P$20") (pintype "bidirectional"))
    )
    (net (code "85") (name "unconnected-(CONN1-DISTRI_VBAT-PadP$21)") (class "Default")
      (node (ref "CONN1") (pin "P$21") (pinfunction "DISTRI_VBAT_P$21") (pintype "bidirectional"))
    )
    (net (code "86") (name "unconnected-(CONN1-DISTRI_VBAT-PadP$23)") (class "Default")
      (node (ref "CONN1") (pin "P$23") (pinfunction "DISTRI_VBAT_P$23") (pintype "bidirectional"))
    )
    (net (code "87") (name "unconnected-(CONN1-DISTRI_VBAT-PadP$26)") (class "Default")
      (node (ref "CONN1") (pin "P$26") (pinfunction "DISTRI_VBAT_P$26") (pintype "bidirectional"))
    )
    (net (code "88") (name "unconnected-(CONN1-DISTRI_VBAT-PadP$28)") (class "Default")
      (node (ref "CONN1") (pin "P$28") (pinfunction "DISTRI_VBAT_P$28") (pintype "bidirectional"))
    )
    (net (code "89") (name "unconnected-(CONN1-DISTRI_VBAT-PadP$29)") (class "Default")
      (node (ref "CONN1") (pin "P$29") (pinfunction "DISTRI_VBAT_P$29") (pintype "bidirectional"))
    )
    (net (code "90") (name "unconnected-(CONN1-DISTRI_VBAT-PadP$31)") (class "Default")
      (node (ref "CONN1") (pin "P$31") (pinfunction "DISTRI_VBAT_P$31") (pintype "bidirectional"))
    )
    (net (code "91") (name "unconnected-(CONN1-GEN_VBATT$35-PadP$35)") (class "Default")
      (node (ref "CONN1") (pin "P$35") (pinfunction "GEN_VBATT$35_P$35") (pintype "bidirectional"))
    )
    (net (code "92") (name "unconnected-(CONN1-GEN_VBATT$36-PadP$36)") (class "Default")
      (node (ref "CONN1") (pin "P$36") (pinfunction "GEN_VBATT$36_P$36") (pintype "bidirectional"))
    )
    (net (code "93") (name "unconnected-(CONN1-P-PadP$59)") (class "Default")
      (node (ref "CONN1") (pin "P$59") (pinfunction "P_P$59") (pintype "bidirectional"))
    )
    (net (code "94") (name "unconnected-(CONN1-PPT_GND-PadP$1)") (class "Default")
      (node (ref "CONN1") (pin "P$1") (pinfunction "PPT_GND_P$1") (pintype "bidirectional"))
    )
    (net (code "95") (name "unconnected-(CONN1-PPT_GND-PadP$3)") (class "Default")
      (node (ref "CONN1") (pin "P$3") (pinfunction "PPT_GND_P$3") (pintype "bidirectional"))
    )
    (net (code "96") (name "unconnected-(CONN1-PPT_GND-PadP$6)") (class "Default")
      (node (ref "CONN1") (pin "P$6") (pinfunction "PPT_GND_P$6") (pintype "bidirectional"))
    )
    (net (code "97") (name "unconnected-(CONN1-PPT_GND-PadP$8)") (class "Default")
      (node (ref "CONN1") (pin "P$8") (pinfunction "PPT_GND_P$8") (pintype "bidirectional"))
    )
    (net (code "98") (name "unconnected-(CONN1-PPT_GND-PadP$9)") (class "Default")
      (node (ref "CONN1") (pin "P$9") (pinfunction "PPT_GND_P$9") (pintype "bidirectional"))
    )
    (net (code "99") (name "unconnected-(CONN1-PPT_GND-PadP$11)") (class "Default")
      (node (ref "CONN1") (pin "P$11") (pinfunction "PPT_GND_P$11") (pintype "bidirectional"))
    )
    (net (code "100") (name "unconnected-(CONN1-PPT_GND-PadP$14)") (class "Default")
      (node (ref "CONN1") (pin "P$14") (pinfunction "PPT_GND_P$14") (pintype "bidirectional"))
    )
    (net (code "101") (name "unconnected-(CONN1-PPT_GND-PadP$16)") (class "Default")
      (node (ref "CONN1") (pin "P$16") (pinfunction "PPT_GND_P$16") (pintype "bidirectional"))
    )
    (net (code "102") (name "unconnected-(CONN1-PPT_VBAT-PadP$2)") (class "Default")
      (node (ref "CONN1") (pin "P$2") (pinfunction "PPT_VBAT_P$2") (pintype "bidirectional"))
    )
    (net (code "103") (name "unconnected-(CONN1-PPT_VBAT-PadP$4)") (class "Default")
      (node (ref "CONN1") (pin "P$4") (pinfunction "PPT_VBAT_P$4") (pintype "bidirectional"))
    )
    (net (code "104") (name "unconnected-(CONN1-PPT_VBAT-PadP$5)") (class "Default")
      (node (ref "CONN1") (pin "P$5") (pinfunction "PPT_VBAT_P$5") (pintype "bidirectional"))
    )
    (net (code "105") (name "unconnected-(CONN1-PPT_VBAT-PadP$7)") (class "Default")
      (node (ref "CONN1") (pin "P$7") (pinfunction "PPT_VBAT_P$7") (pintype "bidirectional"))
    )
    (net (code "106") (name "unconnected-(CONN1-PPT_VBAT-PadP$10)") (class "Default")
      (node (ref "CONN1") (pin "P$10") (pinfunction "PPT_VBAT_P$10") (pintype "bidirectional"))
    )
    (net (code "107") (name "unconnected-(CONN1-PPT_VBAT-PadP$12)") (class "Default")
      (node (ref "CONN1") (pin "P$12") (pinfunction "PPT_VBAT_P$12") (pintype "bidirectional"))
    )
    (net (code "108") (name "unconnected-(CONN1-PPT_VBAT-PadP$13)") (class "Default")
      (node (ref "CONN1") (pin "P$13") (pinfunction "PPT_VBAT_P$13") (pintype "bidirectional"))
    )
    (net (code "109") (name "unconnected-(CONN1-PPT_VBAT-PadP$15)") (class "Default")
      (node (ref "CONN1") (pin "P$15") (pinfunction "PPT_VBAT_P$15") (pintype "bidirectional"))
    )
    (net (code "110") (name "unconnected-(CONN1-PadP$37)") (class "Default")
      (node (ref "CONN1") (pin "P$37") (pinfunction "P$37_P$37") (pintype "bidirectional"))
    )
    (net (code "111") (name "unconnected-(CONN1-PadP$38)") (class "Default")
      (node (ref "CONN1") (pin "P$38") (pinfunction "P$38_P$38") (pintype "bidirectional"))
    )
    (net (code "112") (name "unconnected-(CONN1-PadP$39)") (class "Default")
      (node (ref "CONN1") (pin "P$39") (pinfunction "P$39_P$39") (pintype "bidirectional"))
    )
    (net (code "113") (name "unconnected-(CONN1-PadP$40)") (class "Default")
      (node (ref "CONN1") (pin "P$40") (pinfunction "P$40_P$40") (pintype "bidirectional"))
    )
    (net (code "114") (name "unconnected-(CONN1-PadP$41)") (class "Default")
      (node (ref "CONN1") (pin "P$41") (pinfunction "P$41_P$41") (pintype "bidirectional"))
    )
    (net (code "115") (name "unconnected-(CONN1-PadP$42)") (class "Default")
      (node (ref "CONN1") (pin "P$42") (pinfunction "P$42_P$42") (pintype "bidirectional"))
    )
    (net (code "116") (name "unconnected-(CONN1-PadP$43)") (class "Default")
      (node (ref "CONN1") (pin "P$43") (pinfunction "P$43_P$43") (pintype "bidirectional"))
    )
    (net (code "117") (name "unconnected-(CONN1-PadP$44)") (class "Default")
      (node (ref "CONN1") (pin "P$44") (pinfunction "P$44_P$44") (pintype "bidirectional"))
    )
    (net (code "118") (name "unconnected-(CONN1-PadP$46)") (class "Default")
      (node (ref "CONN1") (pin "P$46") (pinfunction "P$46_P$46") (pintype "bidirectional"))
    )
    (net (code "119") (name "unconnected-(CONN1-PadP$47)") (class "Default")
      (node (ref "CONN1") (pin "P$47") (pinfunction "P$47_P$47") (pintype "bidirectional"))
    )
    (net (code "120") (name "unconnected-(CONN1-PadP$48)") (class "Default")
      (node (ref "CONN1") (pin "P$48") (pinfunction "P$48_P$48") (pintype "bidirectional"))
    )
    (net (code "121") (name "unconnected-(CONN1-PadP$50)") (class "Default")
      (node (ref "CONN1") (pin "P$50") (pinfunction "P$50_P$50") (pintype "bidirectional"))
    )
    (net (code "122") (name "unconnected-(CONN1-PadP$54)") (class "Default")
      (node (ref "CONN1") (pin "P$54") (pinfunction "P$54_P$54") (pintype "bidirectional"))
    )
    (net (code "123") (name "unconnected-(CONN1-PadP$58)") (class "Default")
      (node (ref "CONN1") (pin "P$58") (pinfunction "P$58_P$58") (pintype "bidirectional"))
    )
    (net (code "124") (name "unconnected-(CONN1-PadP$60)") (class "Default")
      (node (ref "CONN1") (pin "P$60") (pinfunction "P$60_P$60") (pintype "bidirectional"))
    )
    (net (code "125") (name "unconnected-(CONN1-PadP$61)") (class "Default")
      (node (ref "CONN1") (pin "P$61") (pinfunction "P$61_P$61") (pintype "bidirectional"))
    )
    (net (code "126") (name "unconnected-(CONN1-PadP$62)") (class "Default")
      (node (ref "CONN1") (pin "P$62") (pinfunction "P$62_P$62") (pintype "bidirectional"))
    )
    (net (code "127") (name "unconnected-(CONN1-PadP$63)") (class "Default")
      (node (ref "CONN1") (pin "P$63") (pinfunction "P$63_P$63") (pintype "bidirectional"))
    )
    (net (code "128") (name "unconnected-(CONN1-PadP$64)") (class "Default")
      (node (ref "CONN1") (pin "P$64") (pinfunction "P$64_P$64") (pintype "bidirectional"))
    )
    (net (code "129") (name "unconnected-(CONN1-PadP$65)") (class "Default")
      (node (ref "CONN1") (pin "P$65") (pinfunction "P$65_P$65") (pintype "bidirectional"))
    )
    (net (code "130") (name "unconnected-(CONN1-PadP$66)") (class "Default")
      (node (ref "CONN1") (pin "P$66") (pinfunction "P$66_P$66") (pintype "bidirectional"))
    )
    (net (code "131") (name "unconnected-(CONN1-PadP$67)") (class "Default")
      (node (ref "CONN1") (pin "P$67") (pinfunction "P$67_P$67") (pintype "bidirectional"))
    )
    (net (code "132") (name "unconnected-(CONN1-PadP$68)") (class "Default")
      (node (ref "CONN1") (pin "P$68") (pinfunction "P$68_P$68") (pintype "bidirectional"))
    )
    (net (code "133") (name "unconnected-(CONN1-PadP$73)") (class "Default")
      (node (ref "CONN1") (pin "P$73") (pinfunction "P$73_P$73") (pintype "bidirectional"))
    )
    (net (code "134") (name "unconnected-(CONN1-PadP$74)") (class "Default")
      (node (ref "CONN1") (pin "P$74") (pinfunction "P$74_P$74") (pintype "bidirectional"))
    )
    (net (code "135") (name "unconnected-(CONN1-PadP$75)") (class "Default")
      (node (ref "CONN1") (pin "P$75") (pinfunction "P$75_P$75") (pintype "bidirectional"))
    )
    (net (code "136") (name "unconnected-(CONN1-PadP$76)") (class "Default")
      (node (ref "CONN1") (pin "P$76") (pinfunction "P$76_P$76") (pintype "bidirectional"))
    )
    (net (code "137") (name "unconnected-(CONN1-PadP$81)") (class "Default")
      (node (ref "CONN1") (pin "P$81") (pinfunction "P$81_P$81") (pintype "bidirectional"))
    )
    (net (code "138") (name "unconnected-(CONN1-PadP$82)") (class "Default")
      (node (ref "CONN1") (pin "P$82") (pinfunction "P$82_P$82") (pintype "bidirectional"))
    )
    (net (code "139") (name "unconnected-(CONN1-PadP$83)") (class "Default")
      (node (ref "CONN1") (pin "P$83") (pinfunction "P$83_P$83") (pintype "bidirectional"))
    )
    (net (code "140") (name "unconnected-(CONN1-PadP$84)") (class "Default")
      (node (ref "CONN1") (pin "P$84") (pinfunction "P$84_P$84") (pintype "bidirectional"))
    )
    (net (code "141") (name "unconnected-(CONN1-PadP$89)") (class "Default")
      (node (ref "CONN1") (pin "P$89") (pinfunction "P$89_P$89") (pintype "bidirectional"))
    )
    (net (code "142") (name "unconnected-(CONN1-PadP$90)") (class "Default")
      (node (ref "CONN1") (pin "P$90") (pinfunction "P$90_P$90") (pintype "bidirectional"))
    )
    (net (code "143") (name "unconnected-(CONN1-PadP$91)") (class "Default")
      (node (ref "CONN1") (pin "P$91") (pinfunction "P$91_P$91") (pintype "bidirectional"))
    )
    (net (code "144") (name "unconnected-(CONN1-PadP$92)") (class "Default")
      (node (ref "CONN1") (pin "P$92") (pinfunction "P$92_P$92") (pintype "bidirectional"))
    )
    (net (code "145") (name "unconnected-(CONN1-PadP$95)") (class "Default")
      (node (ref "CONN1") (pin "P$95") (pinfunction "P$95_P$95") (pintype "bidirectional"))
    )
    (net (code "146") (name "unconnected-(CONN1-PadP$96)") (class "Default")
      (node (ref "CONN1") (pin "P$96") (pinfunction "P$96_P$96") (pintype "bidirectional"))
    )
    (net (code "147") (name "unconnected-(CONN1-RAHS_GND-PadP$94)") (class "Default")
      (node (ref "CONN1") (pin "P$94") (pinfunction "RAHS_GND_P$94") (pintype "bidirectional"))
    )
    (net (code "148") (name "unconnected-(CONN1-RAHS_VBAT-PadP$93)") (class "Default")
      (node (ref "CONN1") (pin "P$93") (pinfunction "RAHS_VBAT_P$93") (pintype "bidirectional"))
    )
    (net (code "149") (name "unconnected-(CONN1-TOPDEPLOY+-PadP$51)") (class "Default")
      (node (ref "CONN1") (pin "P$51") (pinfunction "TOPDEPLOY+_P$51") (pintype "bidirectional"))
    )
    (net (code "150") (name "unconnected-(CONN1-TOPDEPLOY+-PadP$55)") (class "Default")
      (node (ref "CONN1") (pin "P$55") (pinfunction "TOPDEPLOY+_P$55") (pintype "bidirectional"))
    )
    (net (code "151") (name "unconnected-(CONN1-TOPDEPLOY-$52-PadP$52)") (class "Default")
      (node (ref "CONN1") (pin "P$52") (pinfunction "TOPDEPLOY-$52_P$52") (pintype "bidirectional"))
    )
    (net (code "152") (name "unconnected-(CONN1-TOPDEPLOY-$56-PadP$56)") (class "Default")
      (node (ref "CONN1") (pin "P$56") (pinfunction "TOPDEPLOY-$56_P$56") (pintype "bidirectional"))
    )
    (net (code "153") (name "unconnected-(CONN1-WHEEL_GND-PadP$71)") (class "Default")
      (node (ref "CONN1") (pin "P$71") (pinfunction "WHEEL_GND_P$71") (pintype "bidirectional"))
    )
    (net (code "154") (name "unconnected-(CONN1-WHEEL_GND-PadP$72)") (class "Default")
      (node (ref "CONN1") (pin "P$72") (pinfunction "WHEEL_GND_P$72") (pintype "bidirectional"))
    )
    (net (code "155") (name "unconnected-(CONN1-WHEEL_VBAT-PadP$69)") (class "Default")
      (node (ref "CONN1") (pin "P$69") (pinfunction "WHEEL_VBAT_P$69") (pintype "bidirectional"))
    )
    (net (code "156") (name "unconnected-(CONN1-WHEEL_VBAT-PadP$70)") (class "Default")
      (node (ref "CONN1") (pin "P$70") (pinfunction "WHEEL_VBAT_P$70") (pintype "bidirectional"))
    )
    (net (code "157") (name "unconnected-(U3-EVENT1{slash}TXD3-PadP$9)") (class "Default")
      (node (ref "U3") (pin "P$9") (pinfunction "EVENT1/TXD3_P$9") (pintype "bidirectional"))
    )
    (net (code "158") (name "unconnected-(U3-EVENT2{slash}CAN1TX-PadP$7)") (class "Default")
      (node (ref "U3") (pin "P$7") (pinfunction "EVENT2/CAN1TX_P$7") (pintype "bidirectional"))
    )
    (net (code "159") (name "unconnected-(U3-NC-PadP$1)") (class "Default")
      (node (ref "U3") (pin "P$1") (pinfunction "NC_P$1") (pintype "bidirectional"))
    )
    (net (code "160") (name "unconnected-(U3-VARF{slash}CAN1RX-PadP$6)") (class "Default")
      (node (ref "U3") (pin "P$6") (pinfunction "VARF/CAN1RX_P$6") (pintype "bidirectional"))
    )
  )
)
